# MSP430.net
KiCad netlist of a schematic drawn in Altium Designer
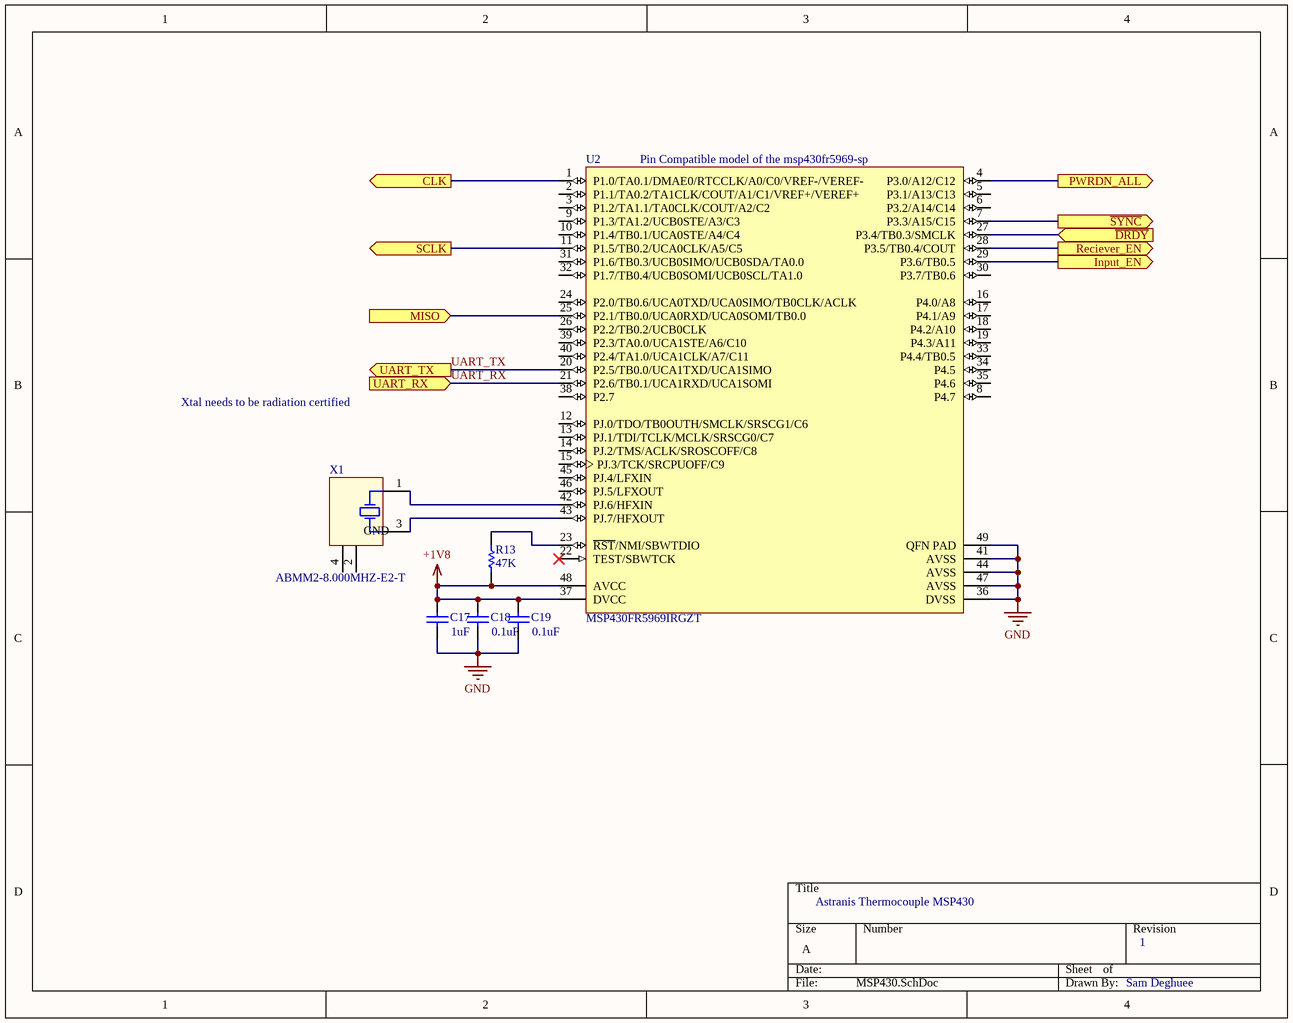
[diagram p0: MSP430.SchDoc]

(export (version "E")
  (design (tool "Eeschema 10.0.6"))
  (components
    (comp (ref "C17")
      (value "1uF")
      (footprint "CAPC0603(1608)100_L")
      (description "0603 (1608 Metric) Chip Capacitor")
      (fields (field (name "Comment") "CAP0603"))
      (libsource (lib "Altium Content Vault") (part "CAP_5"))
    )
    (comp (ref "C18")
      (value "0.1uF")
      (footprint "CAPC0603(1608)100_L")
      (description "0603 (1608 Metric) Chip Capacitor")
      (fields (field (name "Comment") "CAP0603"))
      (libsource (lib "Altium Content Vault") (part "CAP_5"))
    )
    (comp (ref "C19")
      (value "0.1uF")
      (footprint "CAPC0603(1608)100_L")
      (description "0603 (1608 Metric) Chip Capacitor")
      (fields (field (name "Comment") "CAP0603"))
      (libsource (lib "Altium Content Vault") (part "CAP_5"))
    )
    (comp (ref "R13")
      (value "47K")
      (footprint "RESC0603(1608)_L")
      (description "0603 (1608 Metric) Chip Resistor")
      (fields (field (name "Comment") "RES0603"))
      (libsource (lib "Altium Content Vault") (part "RES_3"))
    )
    (comp (ref "U2")
      (value "MSP430FR5969IRGZT")
      (footprint "RGZ0048B_V")
      (fields (field (name "MANUFACTURER") "Texas Instruments"))
      (libsource (lib "Altium Content Vault") (part "TI-MSP430FR586XX-RGZ48"))
    )
    (comp (ref "X1")
      (value "ABMM2-8.000MHZ-E2-T")
      (footprint "ABRA-ABMM2-4_V")
      (fields (field (name "MANUFACTURER") "Abracon"))
      (libsource (lib "Altium Content Vault") (part "ABRA-XTAL_1-3-4"))
    )
  )
  (nets
    (net (code "1") (name "+1V8") (class "Default")
      (node (ref "C17") (pin "2") (pinfunction "2_2") (pintype "passive"))
      (node (ref "C18") (pin "2") (pinfunction "2_2") (pintype "passive"))
      (node (ref "C19") (pin "2") (pinfunction "2_2") (pintype "passive"))
      (node (ref "R13") (pin "2") (pinfunction "2_2") (pintype "passive"))
      (node (ref "U2") (pin "37") (pinfunction "DVCC_37") (pintype "power_in"))
      (node (ref "U2") (pin "48") (pinfunction "AVCC_48") (pintype "power_in"))
    )
    (net (code "2") (name "/CLK") (class "Default")
      (node (ref "U2") (pin "1") (pinfunction "P1.0/TA0.1/DMAE0/RTCCLK/A0/C0/VREF-/VEREF-_1") (pintype "bidirectional"))
    )
    (net (code "3") (name "/Input_EN") (class "Default")
      (node (ref "U2") (pin "29") (pinfunction "P3.6/TB0.5_29") (pintype "bidirectional"))
    )
    (net (code "4") (name "/MISO") (class "Default")
      (node (ref "U2") (pin "25") (pinfunction "P2.1/TB0.0/UCA0RXD/UCA0SOMI/TB0.0_25") (pintype "bidirectional"))
    )
    (net (code "5") (name "/PWRDN_ALL") (class "Default")
      (node (ref "U2") (pin "4") (pinfunction "P3.0/A12/C12_4") (pintype "bidirectional"))
    )
    (net (code "6") (name "/Reciever_EN") (class "Default")
      (node (ref "U2") (pin "28") (pinfunction "P3.5/TB0.4/COUT_28") (pintype "bidirectional"))
    )
    (net (code "7") (name "/SCLK") (class "Default")
      (node (ref "U2") (pin "11") (pinfunction "P1.5/TB0.2/UCA0CLK/A5/C5_11") (pintype "bidirectional"))
    )
    (net (code "8") (name "/UART_RX") (class "Default")
      (node (ref "U2") (pin "21") (pinfunction "P2.6/TB0.1/UCA1RXD/UCA1SOMI_21") (pintype "bidirectional"))
    )
    (net (code "9") (name "/UART_TX") (class "Default")
      (node (ref "U2") (pin "20") (pinfunction "P2.5/TB0.0/UCA1TXD/UCA1SIMO_20") (pintype "bidirectional"))
    )
    (net (code "10") (name "/~{DRDY}") (class "Default")
      (node (ref "U2") (pin "27") (pinfunction "P3.4/TB0.3/SMCLK_27") (pintype "bidirectional"))
    )
    (net (code "11") (name "/~{SYNC}") (class "Default")
      (node (ref "U2") (pin "7") (pinfunction "P3.3/A15/C15_7") (pintype "bidirectional"))
    )
    (net (code "12") (name "GND") (class "Default")
      (node (ref "C17") (pin "1") (pinfunction "1_1") (pintype "passive"))
      (node (ref "C18") (pin "1") (pinfunction "1_1") (pintype "passive"))
      (node (ref "C19") (pin "1") (pinfunction "1_1") (pintype "passive"))
      (node (ref "U2") (pin "36") (pinfunction "DVSS_36") (pintype "power_in"))
      (node (ref "U2") (pin "41") (pinfunction "AVSS_41") (pintype "power_in"))
      (node (ref "U2") (pin "44") (pinfunction "AVSS_44") (pintype "power_in"))
      (node (ref "U2") (pin "47") (pinfunction "AVSS_47") (pintype "power_in"))
      (node (ref "U2") (pin "49") (pinfunction "QFN_PAD_49") (pintype "power_in"))
    )
    (net (code "13") (name "Net-(U2-PJ.6{slash}HFXIN)") (class "Default")
      (node (ref "U2") (pin "42") (pinfunction "PJ.6/HFXIN_42") (pintype "bidirectional"))
      (node (ref "X1") (pin "1") (pinfunction "X1_1") (pintype "passive"))
    )
    (net (code "14") (name "Net-(U2-PJ.7{slash}HFXOUT)") (class "Default")
      (node (ref "U2") (pin "43") (pinfunction "PJ.7/HFXOUT_43") (pintype "bidirectional"))
      (node (ref "X1") (pin "3") (pinfunction "X2_3") (pintype "passive"))
    )
    (net (code "15") (name "Net-(U2-~{RST}{slash}NMI{slash}SBWTDIO)") (class "Default")
      (node (ref "R13") (pin "1") (pinfunction "1_1") (pintype "passive"))
      (node (ref "U2") (pin "23") (pinfunction "~{RST}/NMI/SBWTDIO_23") (pintype "bidirectional"))
    )
    (net (code "16") (name "unconnected-(U2-P1.1{slash}TA0.2{slash}TA1CLK{slash}COUT{slash}A1{slash}C1{slash}VREF+{slash}VEREF+-Pad2)") (class "Default")
      (node (ref "U2") (pin "2") (pinfunction "P1.1/TA0.2/TA1CLK/COUT/A1/C1/VREF+/VEREF+_2") (pintype "bidirectional"))
    )
    (net (code "17") (name "unconnected-(U2-P1.2{slash}TA1.1{slash}TA0CLK{slash}COUT{slash}A2{slash}C2-Pad3)") (class "Default")
      (node (ref "U2") (pin "3") (pinfunction "P1.2/TA1.1/TA0CLK/COUT/A2/C2_3") (pintype "bidirectional"))
    )
    (net (code "18") (name "unconnected-(U2-P1.3{slash}TA1.2{slash}UCB0STE{slash}A3{slash}C3-Pad9)") (class "Default")
      (node (ref "U2") (pin "9") (pinfunction "P1.3/TA1.2/UCB0STE/A3/C3_9") (pintype "bidirectional"))
    )
    (net (code "19") (name "unconnected-(U2-P1.4{slash}TB0.1{slash}UCA0STE{slash}A4{slash}C4-Pad10)") (class "Default")
      (node (ref "U2") (pin "10") (pinfunction "P1.4/TB0.1/UCA0STE/A4/C4_10") (pintype "bidirectional"))
    )
    (net (code "20") (name "unconnected-(U2-P1.6{slash}TB0.3{slash}UCB0SIMO{slash}UCB0SDA{slash}TA0.0-Pad31)") (class "Default")
      (node (ref "U2") (pin "31") (pinfunction "P1.6/TB0.3/UCB0SIMO/UCB0SDA/TA0.0_31") (pintype "bidirectional"))
    )
    (net (code "21") (name "unconnected-(U2-P1.7{slash}TB0.4{slash}UCB0SOMI{slash}UCB0SCL{slash}TA1.0-Pad32)") (class "Default")
      (node (ref "U2") (pin "32") (pinfunction "P1.7/TB0.4/UCB0SOMI/UCB0SCL/TA1.0_32") (pintype "bidirectional"))
    )
    (net (code "22") (name "unconnected-(U2-P2.0{slash}TB0.6{slash}UCA0TXD{slash}UCA0SIMO{slash}TB0CLK{slash}ACLK-Pad24)") (class "Default")
      (node (ref "U2") (pin "24") (pinfunction "P2.0/TB0.6/UCA0TXD/UCA0SIMO/TB0CLK/ACLK_24") (pintype "bidirectional"))
    )
    (net (code "23") (name "unconnected-(U2-P2.2{slash}TB0.2{slash}UCB0CLK-Pad26)") (class "Default")
      (node (ref "U2") (pin "26") (pinfunction "P2.2/TB0.2/UCB0CLK_26") (pintype "bidirectional"))
    )
    (net (code "24") (name "unconnected-(U2-P2.3{slash}TA0.0{slash}UCA1STE{slash}A6{slash}C10-Pad39)") (class "Default")
      (node (ref "U2") (pin "39") (pinfunction "P2.3/TA0.0/UCA1STE/A6/C10_39") (pintype "bidirectional"))
    )
    (net (code "25") (name "unconnected-(U2-P2.4{slash}TA1.0{slash}UCA1CLK{slash}A7{slash}C11-Pad40)") (class "Default")
      (node (ref "U2") (pin "40") (pinfunction "P2.4/TA1.0/UCA1CLK/A7/C11_40") (pintype "bidirectional"))
    )
    (net (code "26") (name "unconnected-(U2-P2.7-Pad38)") (class "Default")
      (node (ref "U2") (pin "38") (pinfunction "P2.7_38") (pintype "bidirectional"))
    )
    (net (code "27") (name "unconnected-(U2-P3.1{slash}A13{slash}C13-Pad5)") (class "Default")
      (node (ref "U2") (pin "5") (pinfunction "P3.1/A13/C13_5") (pintype "bidirectional"))
    )
    (net (code "28") (name "unconnected-(U2-P3.2{slash}A14{slash}C14-Pad6)") (class "Default")
      (node (ref "U2") (pin "6") (pinfunction "P3.2/A14/C14_6") (pintype "bidirectional"))
    )
    (net (code "29") (name "unconnected-(U2-P3.7{slash}TB0.6-Pad30)") (class "Default")
      (node (ref "U2") (pin "30") (pinfunction "P3.7/TB0.6_30") (pintype "bidirectional"))
    )
    (net (code "30") (name "unconnected-(U2-P4.0{slash}A8-Pad16)") (class "Default")
      (node (ref "U2") (pin "16") (pinfunction "P4.0/A8_16") (pintype "bidirectional"))
    )
    (net (code "31") (name "unconnected-(U2-P4.1{slash}A9-Pad17)") (class "Default")
      (node (ref "U2") (pin "17") (pinfunction "P4.1/A9_17") (pintype "bidirectional"))
    )
    (net (code "32") (name "unconnected-(U2-P4.2{slash}A10-Pad18)") (class "Default")
      (node (ref "U2") (pin "18") (pinfunction "P4.2/A10_18") (pintype "bidirectional"))
    )
    (net (code "33") (name "unconnected-(U2-P4.3{slash}A11-Pad19)") (class "Default")
      (node (ref "U2") (pin "19") (pinfunction "P4.3/A11_19") (pintype "bidirectional"))
    )
    (net (code "34") (name "unconnected-(U2-P4.4{slash}TB0.5-Pad33)") (class "Default")
      (node (ref "U2") (pin "33") (pinfunction "P4.4/TB0.5_33") (pintype "bidirectional"))
    )
    (net (code "35") (name "unconnected-(U2-P4.5-Pad34)") (class "Default")
      (node (ref "U2") (pin "34") (pinfunction "P4.5_34") (pintype "bidirectional"))
    )
    (net (code "36") (name "unconnected-(U2-P4.6-Pad35)") (class "Default")
      (node (ref "U2") (pin "35") (pinfunction "P4.6_35") (pintype "bidirectional"))
    )
    (net (code "37") (name "unconnected-(U2-P4.7-Pad8)") (class "Default")
      (node (ref "U2") (pin "8") (pinfunction "P4.7_8") (pintype "bidirectional"))
    )
    (net (code "38") (name "unconnected-(U2-PJ.0{slash}TDO{slash}TB0OUTH{slash}SMCLK{slash}SRSCG1{slash}C6-Pad12)") (class "Default")
      (node (ref "U2") (pin "12") (pinfunction "PJ.0/TDO/TB0OUTH/SMCLK/SRSCG1/C6_12") (pintype "bidirectional"))
    )
    (net (code "39") (name "unconnected-(U2-PJ.1{slash}TDI{slash}TCLK{slash}MCLK{slash}SRSCG0{slash}C7-Pad13)") (class "Default")
      (node (ref "U2") (pin "13") (pinfunction "PJ.1/TDI/TCLK/MCLK/SRSCG0/C7_13") (pintype "bidirectional"))
    )
    (net (code "40") (name "unconnected-(U2-PJ.2{slash}TMS{slash}ACLK{slash}SROSCOFF{slash}C8-Pad14)") (class "Default")
      (node (ref "U2") (pin "14") (pinfunction "PJ.2/TMS/ACLK/SROSCOFF/C8_14") (pintype "bidirectional"))
    )
    (net (code "41") (name "unconnected-(U2-PJ.3{slash}TCK{slash}SRCPUOFF{slash}C9-Pad15)") (class "Default")
      (node (ref "U2") (pin "15") (pinfunction "PJ.3/TCK/SRCPUOFF/C9_15") (pintype "bidirectional"))
    )
    (net (code "42") (name "unconnected-(U2-PJ.4{slash}LFXIN-Pad45)") (class "Default")
      (node (ref "U2") (pin "45") (pinfunction "PJ.4/LFXIN_45") (pintype "bidirectional"))
    )
    (net (code "43") (name "unconnected-(U2-PJ.5{slash}LFXOUT-Pad46)") (class "Default")
      (node (ref "U2") (pin "46") (pinfunction "PJ.5/LFXOUT_46") (pintype "bidirectional"))
    )
    (net (code "44") (name "unconnected-(U2-TEST{slash}SBWTCK-Pad22)") (class "Default")
      (node (ref "U2") (pin "22") (pinfunction "TEST/SBWTCK_22") (pintype "input+no_connect"))
    )
    (net (code "45") (name "unconnected-(X1-GND-Pad2)") (class "Default")
      (node (ref "X1") (pin "2") (pinfunction "GND_2") (pintype "power_in"))
    )
    (net (code "46") (name "unconnected-(X1-GND-Pad4)") (class "Default")
      (node (ref "X1") (pin "4") (pinfunction "GND_4") (pintype "power_in"))
    )
  )
)
